# Clock_transfer.net
KiCad netlist of a schematic drawn in EAGLE
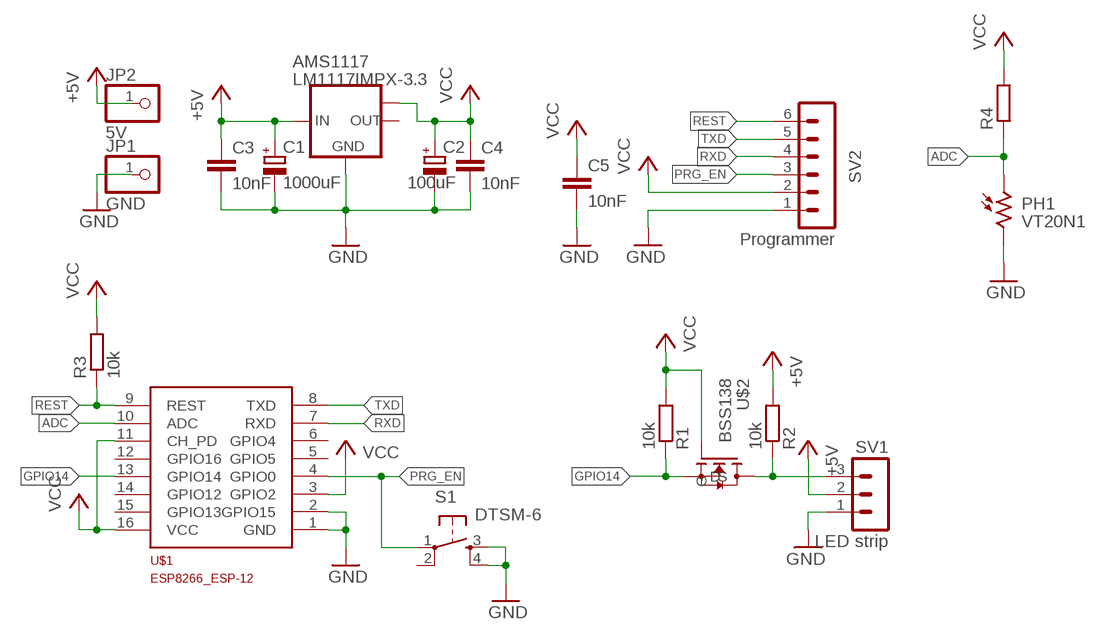
[diagram p0: schematic, sheet 1]

(export (version "E")
  (design (tool "Eeschema 10.0.6"))
  (components
    (comp (ref "AMS1117")
      (value "LM1117IMPX-3.3")
      (footprint "eagle-import:SOT223")
      (libsource (lib "eagle-import") (part "LM1117IMPX-3.3"))
    )
    (comp (ref "C1")
      (value "1000uF")
      (footprint "eagle-import:TT5D11L")
      (libsource (lib "eagle-import") (part "CPOL-EUTT5D11L"))
    )
    (comp (ref "C2")
      (value "100uF")
      (footprint "eagle-import:TT5D7L")
      (libsource (lib "eagle-import") (part "CPOL-EUTT5D7L"))
    )
    (comp (ref "C3")
      (value "10nF")
      (footprint "eagle-import:C0805")
      (libsource (lib "eagle-import") (part "C-EUC0805"))
    )
    (comp (ref "C4")
      (value "10nF")
      (footprint "eagle-import:C0805")
      (libsource (lib "eagle-import") (part "C-EUC0805"))
    )
    (comp (ref "C5")
      (value "10nF")
      (footprint "eagle-import:C0805")
      (libsource (lib "eagle-import") (part "C-EUC0805"))
    )
    (comp (ref "JP1")
      (value "GND")
      (footprint "eagle-import:1X01")
      (libsource (lib "eagle-import") (part "PINHD-1X1"))
    )
    (comp (ref "JP2")
      (value "5V")
      (footprint "eagle-import:1X01")
      (libsource (lib "eagle-import") (part "PINHD-1X1"))
    )
    (comp (ref "PH1")
      (value "VT20N1")
      (footprint "eagle-import:TO46-VT200")
      (libsource (lib "eagle-import") (part "VT20N1"))
    )
    (comp (ref "R1")
      (value "10k")
      (footprint "eagle-import:R0805")
      (libsource (lib "eagle-import") (part "R-EU_R0805"))
    )
    (comp (ref "R2")
      (value "10k")
      (footprint "eagle-import:R0805")
      (libsource (lib "eagle-import") (part "R-EU_R0805"))
    )
    (comp (ref "R3")
      (value "10k")
      (footprint "eagle-import:R0805")
      (libsource (lib "eagle-import") (part "R-EU_R0805"))
    )
    (comp (ref "R4")
      (value "R-EU_R0805")
      (footprint "eagle-import:R0805")
      (libsource (lib "eagle-import") (part "R-EU_R0805"))
    )
    (comp (ref "S1")
      (value "DTSM-6")
      (footprint "eagle-import:DTSM-6")
      (libsource (lib "eagle-import") (part "DTSM-6"))
    )
    (comp (ref "SV1")
      (value "LED strip")
      (footprint "eagle-import:MA03-1")
      (libsource (lib "eagle-import") (part "MA03-1"))
    )
    (comp (ref "SV2")
      (value "Programmer")
      (footprint "eagle-import:MA06-1")
      (libsource (lib "eagle-import") (part "MA06-1"))
    )
    (comp (ref "U$1")
      (value "ESP8266_ESP-12")
      (footprint "eagle-import:ESP8266-ESP12")
      (libsource (lib "eagle-import") (part "ESP8266_ESP-12"))
    )
    (comp (ref "U$2")
      (value "BSS138")
      (footprint "eagle-import:BSS138")
      (fields (field (name "MF") "Fairchild Semiconductor"))
      (libsource (lib "eagle-import") (part "BSS138"))
    )
  )
  (nets
    (net (code "1") (name "+5V") (class "Default")
      (node (ref "AMS1117") (pin "3") (pinfunction "IN_3") (pintype "input"))
      (node (ref "C1") (pin "+") (pinfunction "+_+") (pintype "passive"))
      (node (ref "C3") (pin "1") (pinfunction "1_1") (pintype "passive"))
      (node (ref "JP2") (pin "1") (pinfunction "1_1") (pintype "passive"))
      (node (ref "R2") (pin "2") (pinfunction "2_2") (pintype "passive"))
      (node (ref "SV1") (pin "2") (pinfunction "2_2") (pintype "passive"))
    )
    (net (code "2") (name "ADC") (class "Default")
      (node (ref "PH1") (pin "1") (pinfunction "1_1") (pintype "passive"))
      (node (ref "R4") (pin "1") (pinfunction "1_1") (pintype "passive"))
      (node (ref "U$1") (pin "10") (pinfunction "ADC_10") (pintype "bidirectional"))
    )
    (net (code "3") (name "GND") (class "Default")
      (node (ref "AMS1117") (pin "1") (pinfunction "GND_1") (pintype "input"))
      (node (ref "C1") (pin "-") (pinfunction "-_-") (pintype "passive"))
      (node (ref "C2") (pin "-") (pinfunction "-_-") (pintype "passive"))
      (node (ref "C3") (pin "2") (pinfunction "2_2") (pintype "passive"))
      (node (ref "C4") (pin "2") (pinfunction "2_2") (pintype "passive"))
      (node (ref "C5") (pin "2") (pinfunction "2_2") (pintype "passive"))
      (node (ref "JP1") (pin "1") (pinfunction "1_1") (pintype "passive"))
      (node (ref "PH1") (pin "2") (pinfunction "2_2") (pintype "passive"))
      (node (ref "S1") (pin "3") (pinfunction "3_3") (pintype "passive"))
      (node (ref "S1") (pin "4") (pinfunction "4_4") (pintype "passive"))
      (node (ref "SV1") (pin "1") (pinfunction "1_1") (pintype "passive"))
      (node (ref "SV2") (pin "1") (pinfunction "1_1") (pintype "passive"))
      (node (ref "U$1") (pin "1") (pinfunction "GND_1") (pintype "bidirectional"))
      (node (ref "U$1") (pin "2") (pinfunction "GPIO15_2") (pintype "bidirectional"))
    )
    (net (code "4") (name "GPIO14") (class "Default")
      (node (ref "R1") (pin "1") (pinfunction "1_1") (pintype "passive"))
      (node (ref "U$1") (pin "13") (pinfunction "GPIO14_13") (pintype "bidirectional"))
      (node (ref "U$2") (pin "S") (pinfunction "S_S") (pintype "passive"))
    )
    (net (code "5") (name "Net-(R2-Pad1)") (class "Default")
      (node (ref "R2") (pin "1") (pinfunction "1_1") (pintype "passive"))
      (node (ref "SV1") (pin "3") (pinfunction "3_3") (pintype "passive"))
      (node (ref "U$2") (pin "D") (pinfunction "D_D") (pintype "passive"))
    )
    (net (code "6") (name "PRG_EN") (class "Default")
      (node (ref "S1") (pin "1") (pinfunction "1_1") (pintype "passive"))
      (node (ref "SV2") (pin "3") (pinfunction "3_3") (pintype "passive"))
      (node (ref "U$1") (pin "4") (pinfunction "GPIO0_4") (pintype "bidirectional"))
    )
    (net (code "7") (name "REST") (class "Default")
      (node (ref "R3") (pin "1") (pinfunction "1_1") (pintype "passive"))
      (node (ref "SV2") (pin "6") (pinfunction "6_6") (pintype "passive"))
      (node (ref "U$1") (pin "9") (pinfunction "REST_9") (pintype "bidirectional"))
    )
    (net (code "8") (name "RXD") (class "Default")
      (node (ref "SV2") (pin "4") (pinfunction "4_4") (pintype "passive"))
      (node (ref "U$1") (pin "7") (pinfunction "RXD_7") (pintype "bidirectional"))
    )
    (net (code "9") (name "TXD") (class "Default")
      (node (ref "SV2") (pin "5") (pinfunction "5_5") (pintype "passive"))
      (node (ref "U$1") (pin "8") (pinfunction "TXD_8") (pintype "bidirectional"))
    )
    (net (code "10") (name "VCC") (class "Default")
      (node (ref "AMS1117") (pin "TAB") (pinfunction "OUT1_TAB") (pintype "passive"))
      (node (ref "C2") (pin "+") (pinfunction "+_+") (pintype "passive"))
      (node (ref "C4") (pin "1") (pinfunction "1_1") (pintype "passive"))
      (node (ref "C5") (pin "1") (pinfunction "1_1") (pintype "passive"))
      (node (ref "R1") (pin "2") (pinfunction "2_2") (pintype "passive"))
      (node (ref "R3") (pin "2") (pinfunction "2_2") (pintype "passive"))
      (node (ref "R4") (pin "2") (pinfunction "2_2") (pintype "passive"))
      (node (ref "SV2") (pin "2") (pinfunction "2_2") (pintype "passive"))
      (node (ref "U$1") (pin "11") (pinfunction "CH_PD_11") (pintype "bidirectional"))
      (node (ref "U$1") (pin "16") (pinfunction "VCC_16") (pintype "bidirectional"))
      (node (ref "U$1") (pin "3") (pinfunction "GPIO2_3") (pintype "bidirectional"))
      (node (ref "U$2") (pin "G") (pinfunction "G_G") (pintype "passive"))
    )
    (net (code "11") (name "unconnected-(AMS1117-OUT-Pad2)") (class "Default")
      (node (ref "AMS1117") (pin "2") (pinfunction "OUT_2") (pintype "passive"))
    )
    (net (code "12") (name "unconnected-(S1-Pad2)") (class "Default")
      (node (ref "S1") (pin "2") (pinfunction "2_2") (pintype "passive"))
    )
    (net (code "13") (name "unconnected-(U$1-GPIO4-Pad6)") (class "Default")
      (node (ref "U$1") (pin "6") (pinfunction "GPIO4_6") (pintype "bidirectional"))
    )
    (net (code "14") (name "unconnected-(U$1-GPIO5-Pad5)") (class "Default")
      (node (ref "U$1") (pin "5") (pinfunction "GPIO5_5") (pintype "bidirectional"))
    )
    (net (code "15") (name "unconnected-(U$1-GPIO12-Pad14)") (class "Default")
      (node (ref "U$1") (pin "14") (pinfunction "GPIO12_14") (pintype "bidirectional"))
    )
    (net (code "16") (name "unconnected-(U$1-GPIO13-Pad15)") (class "Default")
      (node (ref "U$1") (pin "15") (pinfunction "GPIO13_15") (pintype "bidirectional"))
    )
    (net (code "17") (name "unconnected-(U$1-GPIO16-Pad12)") (class "Default")
      (node (ref "U$1") (pin "12") (pinfunction "GPIO16_12") (pintype "bidirectional"))
    )
  )
)
